# signal_processor_design_of_optimizing_UA.net
KiCad netlist of a schematic drawn in Altium Designer
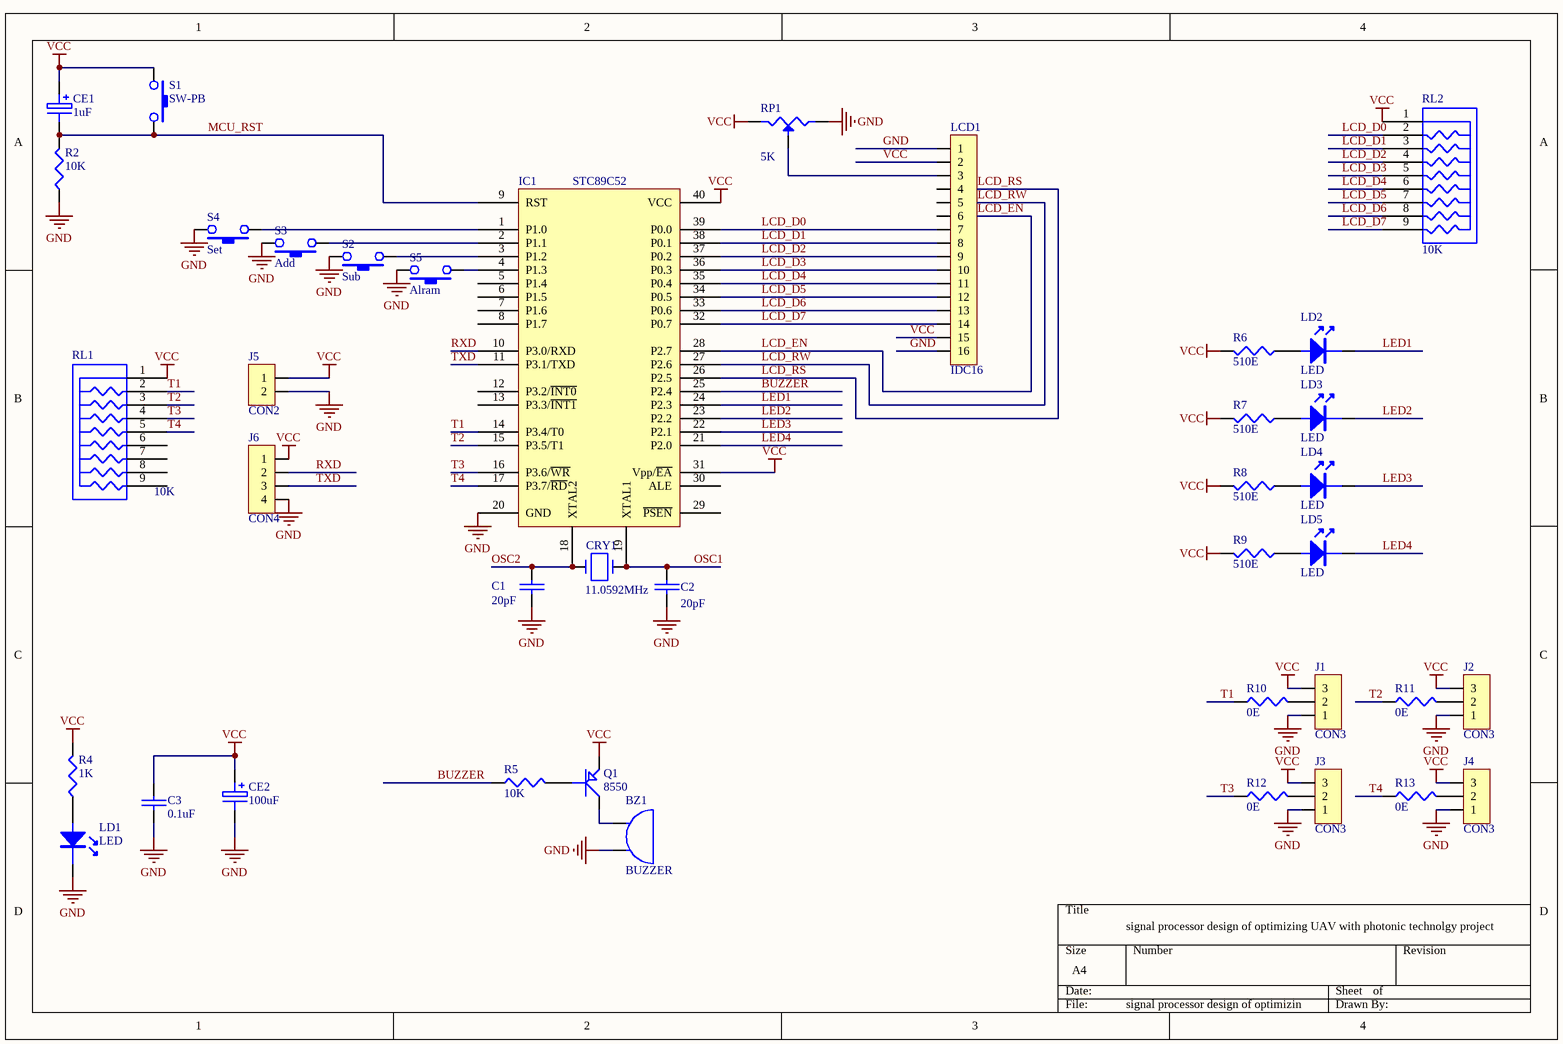
[diagram p0: signal processor design of optimizing UAV with photonic technolgy project.SchDoc]

(export (version "E")
  (design (tool "Eeschema 10.0.6"))
  (components
    (comp (ref "BZ1") (value "BUZZER") (footprint "BUZZER1") (libsource (lib "Sch1") (part "BUZZER")))
    (comp (ref "C1")
      (value "20pF")
      (footprint "RAD0.1")
      (description "Capacitor")
      (libsource (lib "*") (part "CAP"))
    )
    (comp (ref "C2")
      (value "20pF")
      (footprint "RAD0.1")
      (description "Capacitor")
      (libsource (lib "*") (part "CAP"))
    )
    (comp (ref "C3") (value "0.1uF") (footprint "RAD0.1") (libsource (lib "Sch1") (part "CAP")))
    (comp (ref "CE1") (value "1uF") (footprint "RB.1/.1L") (libsource (lib "Sch1") (part "ELECTRO1")))
    (comp (ref "CE2") (value "100uF") (footprint "RB.1/.2") (libsource (lib "Sch1") (part "ELECTRO1")))
    (comp (ref "CRY1") (value "11.0592MHz") (footprint "XTAL1") (libsource (lib "*") (part "CRYSTAL")))
    (comp (ref "IC1") (value "STC89C52") (footprint "DIP40") (libsource (lib "Sch") (part "AT89C51")))
    (comp (ref "J1") (value "CON3") (footprint "HJ3P2.54") (libsource (lib "Sch1") (part "CON3")))
    (comp (ref "J2") (value "CON3") (footprint "HJ3P2.54") (libsource (lib "Sch1") (part "CON3")))
    (comp (ref "J3") (value "CON3") (footprint "HJ3P2.54") (libsource (lib "Sch1") (part "CON3")))
    (comp (ref "J4") (value "CON3") (footprint "HJ3P2.54") (libsource (lib "Sch1") (part "CON3")))
    (comp (ref "J5") (value "CON2") (footprint "HJ2P2.54") (libsource (lib "Sch1") (part "CON2")))
    (comp (ref "J6") (value "CON4") (footprint "HJ4P2.54") (libsource (lib "Sch1") (part "CON4")))
    (comp (ref "LCD1") (value "IDC16") (footprint "LCD1602A") (libsource (lib "Sch1") (part "CON16")))
    (comp (ref "LD1") (value "LED") (footprint "LEDF3") (libsource (lib "Sch1") (part "LED")))
    (comp (ref "LD2") (value "LED") (footprint "LEDF3") (libsource (lib "Sch1") (part "LED")))
    (comp (ref "LD3") (value "LED") (footprint "LEDF3") (libsource (lib "Sch1") (part "LED")))
    (comp (ref "LD4") (value "LED") (footprint "LEDF3") (libsource (lib "Sch1") (part "LED")))
    (comp (ref "LD5") (value "LED") (footprint "LEDF3") (libsource (lib "Sch1") (part "LED")))
    (comp (ref "Q1") (value "8550") (footprint "TR-EBC") (libsource (lib "Sch1") (part "PNP1")))
    (comp (ref "R2") (value "10K") (footprint "AXIAL0.3") (libsource (lib "Sch1") (part "RES1")))
    (comp (ref "R4") (value "1K") (footprint "AXIAL0.3") (libsource (lib "Sch1") (part "RES1")))
    (comp (ref "R5") (value "10K") (footprint "AXIAL0.3") (libsource (lib "Sch1") (part "RES1")))
    (comp (ref "R6") (value "510E") (footprint "AXIAL0.3") (libsource (lib "Sch1") (part "RES1")))
    (comp (ref "R7") (value "510E") (footprint "AXIAL0.3") (libsource (lib "Sch1") (part "RES1")))
    (comp (ref "R8") (value "510E") (footprint "AXIAL0.3") (libsource (lib "Sch1") (part "RES1")))
    (comp (ref "R9") (value "510E") (footprint "AXIAL0.3") (libsource (lib "Sch1") (part "RES1")))
    (comp (ref "R10") (value "0E") (footprint "AXIAL0.3") (libsource (lib "Sch1") (part "RES1")))
    (comp (ref "R11") (value "0E") (footprint "AXIAL0.3") (libsource (lib "Sch1") (part "RES1")))
    (comp (ref "R12") (value "0E") (footprint "AXIAL0.3") (libsource (lib "Sch1") (part "RES1")))
    (comp (ref "R13") (value "0E") (footprint "AXIAL0.3") (libsource (lib "Sch1") (part "RES1")))
    (comp (ref "RL1") (value "10K") (footprint "RES9P") (libsource (lib "Sch1") (part "RESL1")))
    (comp (ref "RL2") (value "10K") (footprint "RES9P") (libsource (lib "Sch1") (part "RESL1")))
    (comp (ref "RP1") (value "5K") (footprint "WR1") (libsource (lib "Sch1") (part "POT1")))
    (comp (ref "S1") (value "SW-PB") (footprint "SW-PB4DS") (libsource (lib "Sch1") (part "SW-PB")))
    (comp (ref "S2") (value "Sub") (footprint "SW-PB4DS") (libsource (lib "Sch1") (part "SW-PB")))
    (comp (ref "S3") (value "Add") (footprint "SW-PB4DS") (libsource (lib "Sch1") (part "SW-PB")))
    (comp (ref "S4") (value "Set") (footprint "SW-PB4DS") (libsource (lib "Sch1") (part "SW-PB")))
    (comp (ref "S5") (value "Alram") (footprint "SW-PB4DS") (libsource (lib "Sch1") (part "SW-PB")))
  )
  (nets
    (net (code "1") (name "/BUZZER") (class "Default")
      (node (ref "IC1") (pin "25") (pinfunction "P2.4_25") (pintype "passive"))
      (node (ref "R5") (pin "1") (pintype "passive"))
    )
    (net (code "2") (name "/LCD_D0") (class "Default")
      (node (ref "IC1") (pin "39") (pinfunction "P0.0_39") (pintype "passive"))
      (node (ref "LCD1") (pin "7") (pinfunction "7_7") (pintype "passive"))
      (node (ref "RL2") (pin "2") (pinfunction "2_2") (pintype "passive"))
    )
    (net (code "3") (name "/LCD_D1") (class "Default")
      (node (ref "IC1") (pin "38") (pinfunction "P0.1_38") (pintype "passive"))
      (node (ref "LCD1") (pin "8") (pinfunction "8_8") (pintype "passive"))
      (node (ref "RL2") (pin "3") (pinfunction "3_3") (pintype "passive"))
    )
    (net (code "4") (name "/LCD_D2") (class "Default")
      (node (ref "IC1") (pin "37") (pinfunction "P0.2_37") (pintype "passive"))
      (node (ref "LCD1") (pin "9") (pinfunction "9_9") (pintype "passive"))
      (node (ref "RL2") (pin "4") (pinfunction "4_4") (pintype "passive"))
    )
    (net (code "5") (name "/LCD_D3") (class "Default")
      (node (ref "IC1") (pin "36") (pinfunction "P0.3_36") (pintype "passive"))
      (node (ref "LCD1") (pin "10") (pinfunction "10_10") (pintype "passive"))
      (node (ref "RL2") (pin "5") (pinfunction "5_5") (pintype "passive"))
    )
    (net (code "6") (name "/LCD_D4") (class "Default")
      (node (ref "IC1") (pin "35") (pinfunction "P0.4_35") (pintype "passive"))
      (node (ref "LCD1") (pin "11") (pinfunction "11_11") (pintype "passive"))
      (node (ref "RL2") (pin "6") (pinfunction "6_6") (pintype "passive"))
    )
    (net (code "7") (name "/LCD_D5") (class "Default")
      (node (ref "IC1") (pin "34") (pinfunction "P0.5_34") (pintype "passive"))
      (node (ref "LCD1") (pin "12") (pinfunction "12_12") (pintype "passive"))
      (node (ref "RL2") (pin "7") (pinfunction "7_7") (pintype "passive"))
    )
    (net (code "8") (name "/LCD_D6") (class "Default")
      (node (ref "IC1") (pin "33") (pinfunction "P0.6_33") (pintype "passive"))
      (node (ref "LCD1") (pin "13") (pinfunction "13_13") (pintype "passive"))
      (node (ref "RL2") (pin "8") (pinfunction "8_8") (pintype "passive"))
    )
    (net (code "9") (name "/LCD_D7") (class "Default")
      (node (ref "IC1") (pin "32") (pinfunction "P0.7_32") (pintype "passive"))
      (node (ref "LCD1") (pin "14") (pinfunction "14_14") (pintype "passive"))
      (node (ref "RL2") (pin "9") (pinfunction "9_9") (pintype "passive"))
    )
    (net (code "10") (name "/LCD_EN") (class "Default")
      (node (ref "IC1") (pin "28") (pinfunction "P2.7_28") (pintype "passive"))
    )
    (net (code "11") (name "/LCD_RS") (class "Default")
      (node (ref "IC1") (pin "26") (pinfunction "P2.5_26") (pintype "passive"))
    )
    (net (code "12") (name "/LCD_RW") (class "Default")
      (node (ref "IC1") (pin "27") (pinfunction "P2.6_27") (pintype "passive"))
    )
    (net (code "13") (name "/LED1") (class "Default")
      (node (ref "IC1") (pin "24") (pinfunction "P2.3_24") (pintype "passive"))
      (node (ref "LD2") (pin "K") (pintype "passive"))
    )
    (net (code "14") (name "/LED2") (class "Default")
      (node (ref "IC1") (pin "23") (pinfunction "P2.2_23") (pintype "passive"))
      (node (ref "LD3") (pin "K") (pintype "passive"))
    )
    (net (code "15") (name "/LED3") (class "Default")
      (node (ref "IC1") (pin "22") (pinfunction "P2.1_22") (pintype "passive"))
      (node (ref "LD4") (pin "K") (pintype "passive"))
    )
    (net (code "16") (name "/LED4") (class "Default")
      (node (ref "IC1") (pin "21") (pinfunction "P2.0_21") (pintype "passive"))
      (node (ref "LD5") (pin "K") (pintype "passive"))
    )
    (net (code "17") (name "/MCU_RST") (class "Default")
      (node (ref "CE1") (pin "2") (pintype "passive"))
      (node (ref "IC1") (pin "9") (pinfunction "RST_9") (pintype "passive"))
      (node (ref "R2") (pin "2") (pintype "passive"))
      (node (ref "S1") (pin "2") (pintype "passive"))
    )
    (net (code "18") (name "/OSC1") (class "Default")
      (node (ref "C2") (pin "1") (pinfunction "1_1") (pintype "passive"))
      (node (ref "CRY1") (pin "2") (pinfunction "2_2") (pintype "passive"))
      (node (ref "IC1") (pin "19") (pinfunction "XTAL1_19") (pintype "passive"))
    )
    (net (code "19") (name "/OSC2") (class "Default")
      (node (ref "C1") (pin "1") (pinfunction "1_1") (pintype "passive"))
      (node (ref "CRY1") (pin "1") (pinfunction "1_1") (pintype "passive"))
      (node (ref "IC1") (pin "18") (pinfunction "XTAL2_18") (pintype "passive"))
    )
    (net (code "20") (name "/RXD") (class "Default")
      (node (ref "IC1") (pin "10") (pinfunction "P3.0/RXD_10") (pintype "passive"))
      (node (ref "J6") (pin "2") (pinfunction "2_2") (pintype "passive"))
    )
    (net (code "21") (name "/T1") (class "Default")
      (node (ref "IC1") (pin "14") (pinfunction "P3.4/T0_14") (pintype "passive"))
      (node (ref "R10") (pin "1") (pintype "passive"))
      (node (ref "RL1") (pin "2") (pinfunction "2_2") (pintype "passive"))
    )
    (net (code "22") (name "/T2") (class "Default")
      (node (ref "IC1") (pin "15") (pinfunction "P3.5/T1_15") (pintype "passive"))
      (node (ref "R11") (pin "1") (pintype "passive"))
      (node (ref "RL1") (pin "3") (pinfunction "3_3") (pintype "passive"))
    )
    (net (code "23") (name "/T3") (class "Default")
      (node (ref "IC1") (pin "16") (pinfunction "P3.6/~{WR}_16") (pintype "passive"))
      (node (ref "R12") (pin "1") (pintype "passive"))
      (node (ref "RL1") (pin "4") (pinfunction "4_4") (pintype "passive"))
    )
    (net (code "24") (name "/T4") (class "Default")
      (node (ref "IC1") (pin "17") (pinfunction "P3.7/~{RD}_17") (pintype "passive"))
      (node (ref "R13") (pin "1") (pintype "passive"))
      (node (ref "RL1") (pin "5") (pinfunction "5_5") (pintype "passive"))
    )
    (net (code "25") (name "/TXD") (class "Default")
      (node (ref "IC1") (pin "11") (pinfunction "P3.1/TXD_11") (pintype "passive"))
      (node (ref "J6") (pin "3") (pinfunction "3_3") (pintype "passive"))
    )
    (net (code "26") (name "GND") (class "Default")
      (node (ref "BZ1") (pin "2") (pintype "passive"))
      (node (ref "C1") (pin "2") (pinfunction "2_2") (pintype "passive"))
      (node (ref "C2") (pin "2") (pinfunction "2_2") (pintype "passive"))
      (node (ref "C3") (pin "2") (pintype "passive"))
      (node (ref "CE2") (pin "2") (pintype "passive"))
      (node (ref "IC1") (pin "20") (pinfunction "GND_20") (pintype "passive"))
      (node (ref "J1") (pin "1") (pinfunction "1_1") (pintype "passive"))
      (node (ref "J2") (pin "1") (pinfunction "1_1") (pintype "passive"))
      (node (ref "J3") (pin "1") (pinfunction "1_1") (pintype "passive"))
      (node (ref "J4") (pin "1") (pinfunction "1_1") (pintype "passive"))
      (node (ref "J5") (pin "2") (pinfunction "2_2") (pintype "passive"))
      (node (ref "J6") (pin "4") (pinfunction "4_4") (pintype "passive"))
      (node (ref "LCD1") (pin "1") (pinfunction "1_1") (pintype "passive"))
      (node (ref "LCD1") (pin "16") (pinfunction "16_16") (pintype "passive"))
      (node (ref "LD1") (pin "K") (pintype "passive"))
      (node (ref "R2") (pin "1") (pintype "passive"))
      (node (ref "RP1") (pin "2") (pintype "passive"))
      (node (ref "S2") (pin "1") (pintype "passive"))
      (node (ref "S3") (pin "1") (pintype "passive"))
      (node (ref "S4") (pin "1") (pintype "passive"))
      (node (ref "S5") (pin "1") (pintype "passive"))
    )
    (net (code "27") (name "Net-(BZ1-Pad1)") (class "Default")
      (node (ref "BZ1") (pin "1") (pintype "passive"))
      (node (ref "Q1") (pin "COLL") (pinfunction "COLL_COLL") (pintype "passive"))
    )
    (net (code "28") (name "Net-(IC1-P1.0)") (class "Default")
      (node (ref "IC1") (pin "1") (pinfunction "P1.0_1") (pintype "passive"))
      (node (ref "S4") (pin "2") (pintype "passive"))
    )
    (net (code "29") (name "Net-(IC1-P1.1)") (class "Default")
      (node (ref "IC1") (pin "2") (pinfunction "P1.1_2") (pintype "passive"))
      (node (ref "S3") (pin "2") (pintype "passive"))
    )
    (net (code "30") (name "Net-(IC1-P1.2)") (class "Default")
      (node (ref "IC1") (pin "3") (pinfunction "P1.2_3") (pintype "passive"))
      (node (ref "S2") (pin "2") (pintype "passive"))
    )
    (net (code "31") (name "Net-(IC1-P1.3)") (class "Default")
      (node (ref "IC1") (pin "4") (pinfunction "P1.3_4") (pintype "passive"))
      (node (ref "S5") (pin "2") (pintype "passive"))
    )
    (net (code "32") (name "Net-(J1-Pad2)") (class "Default")
      (node (ref "J1") (pin "2") (pinfunction "2_2") (pintype "passive"))
      (node (ref "R10") (pin "2") (pintype "passive"))
    )
    (net (code "33") (name "Net-(J2-Pad2)") (class "Default")
      (node (ref "J2") (pin "2") (pinfunction "2_2") (pintype "passive"))
      (node (ref "R11") (pin "2") (pintype "passive"))
    )
    (net (code "34") (name "Net-(J3-Pad2)") (class "Default")
      (node (ref "J3") (pin "2") (pinfunction "2_2") (pintype "passive"))
      (node (ref "R12") (pin "2") (pintype "passive"))
    )
    (net (code "35") (name "Net-(J4-Pad2)") (class "Default")
      (node (ref "J4") (pin "2") (pinfunction "2_2") (pintype "passive"))
      (node (ref "R13") (pin "2") (pintype "passive"))
    )
    (net (code "36") (name "Net-(LCD1-Pad3)") (class "Default")
      (node (ref "LCD1") (pin "3") (pinfunction "3_3") (pintype "passive"))
      (node (ref "RP1") (pin "W") (pintype "passive"))
    )
    (net (code "37") (name "Net-(LD1-PadA)") (class "Default")
      (node (ref "LD1") (pin "A") (pintype "passive"))
      (node (ref "R4") (pin "1") (pintype "passive"))
    )
    (net (code "38") (name "Net-(LD2-PadA)") (class "Default")
      (node (ref "LD2") (pin "A") (pintype "passive"))
      (node (ref "R6") (pin "1") (pintype "passive"))
    )
    (net (code "39") (name "Net-(LD3-PadA)") (class "Default")
      (node (ref "LD3") (pin "A") (pintype "passive"))
      (node (ref "R7") (pin "1") (pintype "passive"))
    )
    (net (code "40") (name "Net-(LD4-PadA)") (class "Default")
      (node (ref "LD4") (pin "A") (pintype "passive"))
      (node (ref "R8") (pin "1") (pintype "passive"))
    )
    (net (code "41") (name "Net-(LD5-PadA)") (class "Default")
      (node (ref "LD5") (pin "A") (pintype "passive"))
      (node (ref "R9") (pin "1") (pintype "passive"))
    )
    (net (code "42") (name "Net-(Q1-PadBASE)") (class "Default")
      (node (ref "Q1") (pin "BASE") (pinfunction "BASE_BASE") (pintype "passive"))
      (node (ref "R5") (pin "2") (pintype "passive"))
    )
    (net (code "43") (name "VCC") (class "Default")
      (node (ref "C3") (pin "1") (pintype "passive"))
      (node (ref "CE1") (pin "1") (pintype "passive"))
      (node (ref "CE2") (pin "1") (pintype "passive"))
      (node (ref "IC1") (pin "31") (pinfunction "Vpp/~{EA}_31") (pintype "passive"))
      (node (ref "IC1") (pin "40") (pinfunction "VCC_40") (pintype "passive"))
      (node (ref "J1") (pin "3") (pinfunction "3_3") (pintype "passive"))
      (node (ref "J2") (pin "3") (pinfunction "3_3") (pintype "passive"))
      (node (ref "J3") (pin "3") (pinfunction "3_3") (pintype "passive"))
      (node (ref "J4") (pin "3") (pinfunction "3_3") (pintype "passive"))
      (node (ref "J5") (pin "1") (pinfunction "1_1") (pintype "passive"))
      (node (ref "J6") (pin "1") (pinfunction "1_1") (pintype "passive"))
      (node (ref "LCD1") (pin "15") (pinfunction "15_15") (pintype "passive"))
      (node (ref "LCD1") (pin "2") (pinfunction "2_2") (pintype "passive"))
      (node (ref "Q1") (pin "EMIT") (pinfunction "EMIT_EMIT") (pintype "passive"))
      (node (ref "R4") (pin "2") (pintype "passive"))
      (node (ref "R6") (pin "2") (pintype "passive"))
      (node (ref "R7") (pin "2") (pintype "passive"))
      (node (ref "R8") (pin "2") (pintype "passive"))
      (node (ref "R9") (pin "2") (pintype "passive"))
      (node (ref "RL1") (pin "1") (pinfunction "1_1") (pintype "passive"))
      (node (ref "RL2") (pin "1") (pinfunction "1_1") (pintype "passive"))
      (node (ref "RP1") (pin "1") (pintype "passive"))
      (node (ref "S1") (pin "1") (pintype "passive"))
    )
    (net (code "44") (name "unconnected-(IC1-ALE-Pad30)") (class "Default")
      (node (ref "IC1") (pin "30") (pinfunction "ALE_30") (pintype "passive"))
    )
    (net (code "45") (name "unconnected-(IC1-P1.4-Pad5)") (class "Default")
      (node (ref "IC1") (pin "5") (pinfunction "P1.4_5") (pintype "passive"))
    )
    (net (code "46") (name "unconnected-(IC1-P1.5-Pad6)") (class "Default")
      (node (ref "IC1") (pin "6") (pinfunction "P1.5_6") (pintype "passive"))
    )
    (net (code "47") (name "unconnected-(IC1-P1.6-Pad7)") (class "Default")
      (node (ref "IC1") (pin "7") (pinfunction "P1.6_7") (pintype "passive"))
    )
    (net (code "48") (name "unconnected-(IC1-P1.7-Pad8)") (class "Default")
      (node (ref "IC1") (pin "8") (pinfunction "P1.7_8") (pintype "passive"))
    )
    (net (code "49") (name "unconnected-(IC1-P3.2{slash}~{INT0}-Pad12)") (class "Default")
      (node (ref "IC1") (pin "12") (pinfunction "P3.2/~{INT0}_12") (pintype "passive"))
    )
    (net (code "50") (name "unconnected-(IC1-P3.3{slash}~{INT1}-Pad13)") (class "Default")
      (node (ref "IC1") (pin "13") (pinfunction "P3.3/~{INT1}_13") (pintype "passive"))
    )
    (net (code "51") (name "unconnected-(IC1-~{PSEN}-Pad29)") (class "Default")
      (node (ref "IC1") (pin "29") (pinfunction "~{PSEN}_29") (pintype "passive"))
    )
    (net (code "52") (name "unconnected-(LCD1-Pad4)") (class "Default")
      (node (ref "LCD1") (pin "4") (pinfunction "4_4") (pintype "passive"))
    )
    (net (code "53") (name "unconnected-(LCD1-Pad5)") (class "Default")
      (node (ref "LCD1") (pin "5") (pinfunction "5_5") (pintype "passive"))
    )
    (net (code "54") (name "unconnected-(LCD1-Pad6)") (class "Default")
      (node (ref "LCD1") (pin "6") (pinfunction "6_6") (pintype "passive"))
    )
    (net (code "55") (name "unconnected-(RL1-Pad6)") (class "Default")
      (node (ref "RL1") (pin "6") (pinfunction "6_6") (pintype "passive"))
    )
    (net (code "56") (name "unconnected-(RL1-Pad7)") (class "Default")
      (node (ref "RL1") (pin "7") (pinfunction "7_7") (pintype "passive"))
    )
    (net (code "57") (name "unconnected-(RL1-Pad8)") (class "Default")
      (node (ref "RL1") (pin "8") (pinfunction "8_8") (pintype "passive"))
    )
    (net (code "58") (name "unconnected-(RL1-Pad9)") (class "Default")
      (node (ref "RL1") (pin "9") (pinfunction "9_9") (pintype "passive"))
    )
  )
)
